# Hardverski_dizajn_ver2.net
KiCad netlist of a schematic drawn in EasyEDA
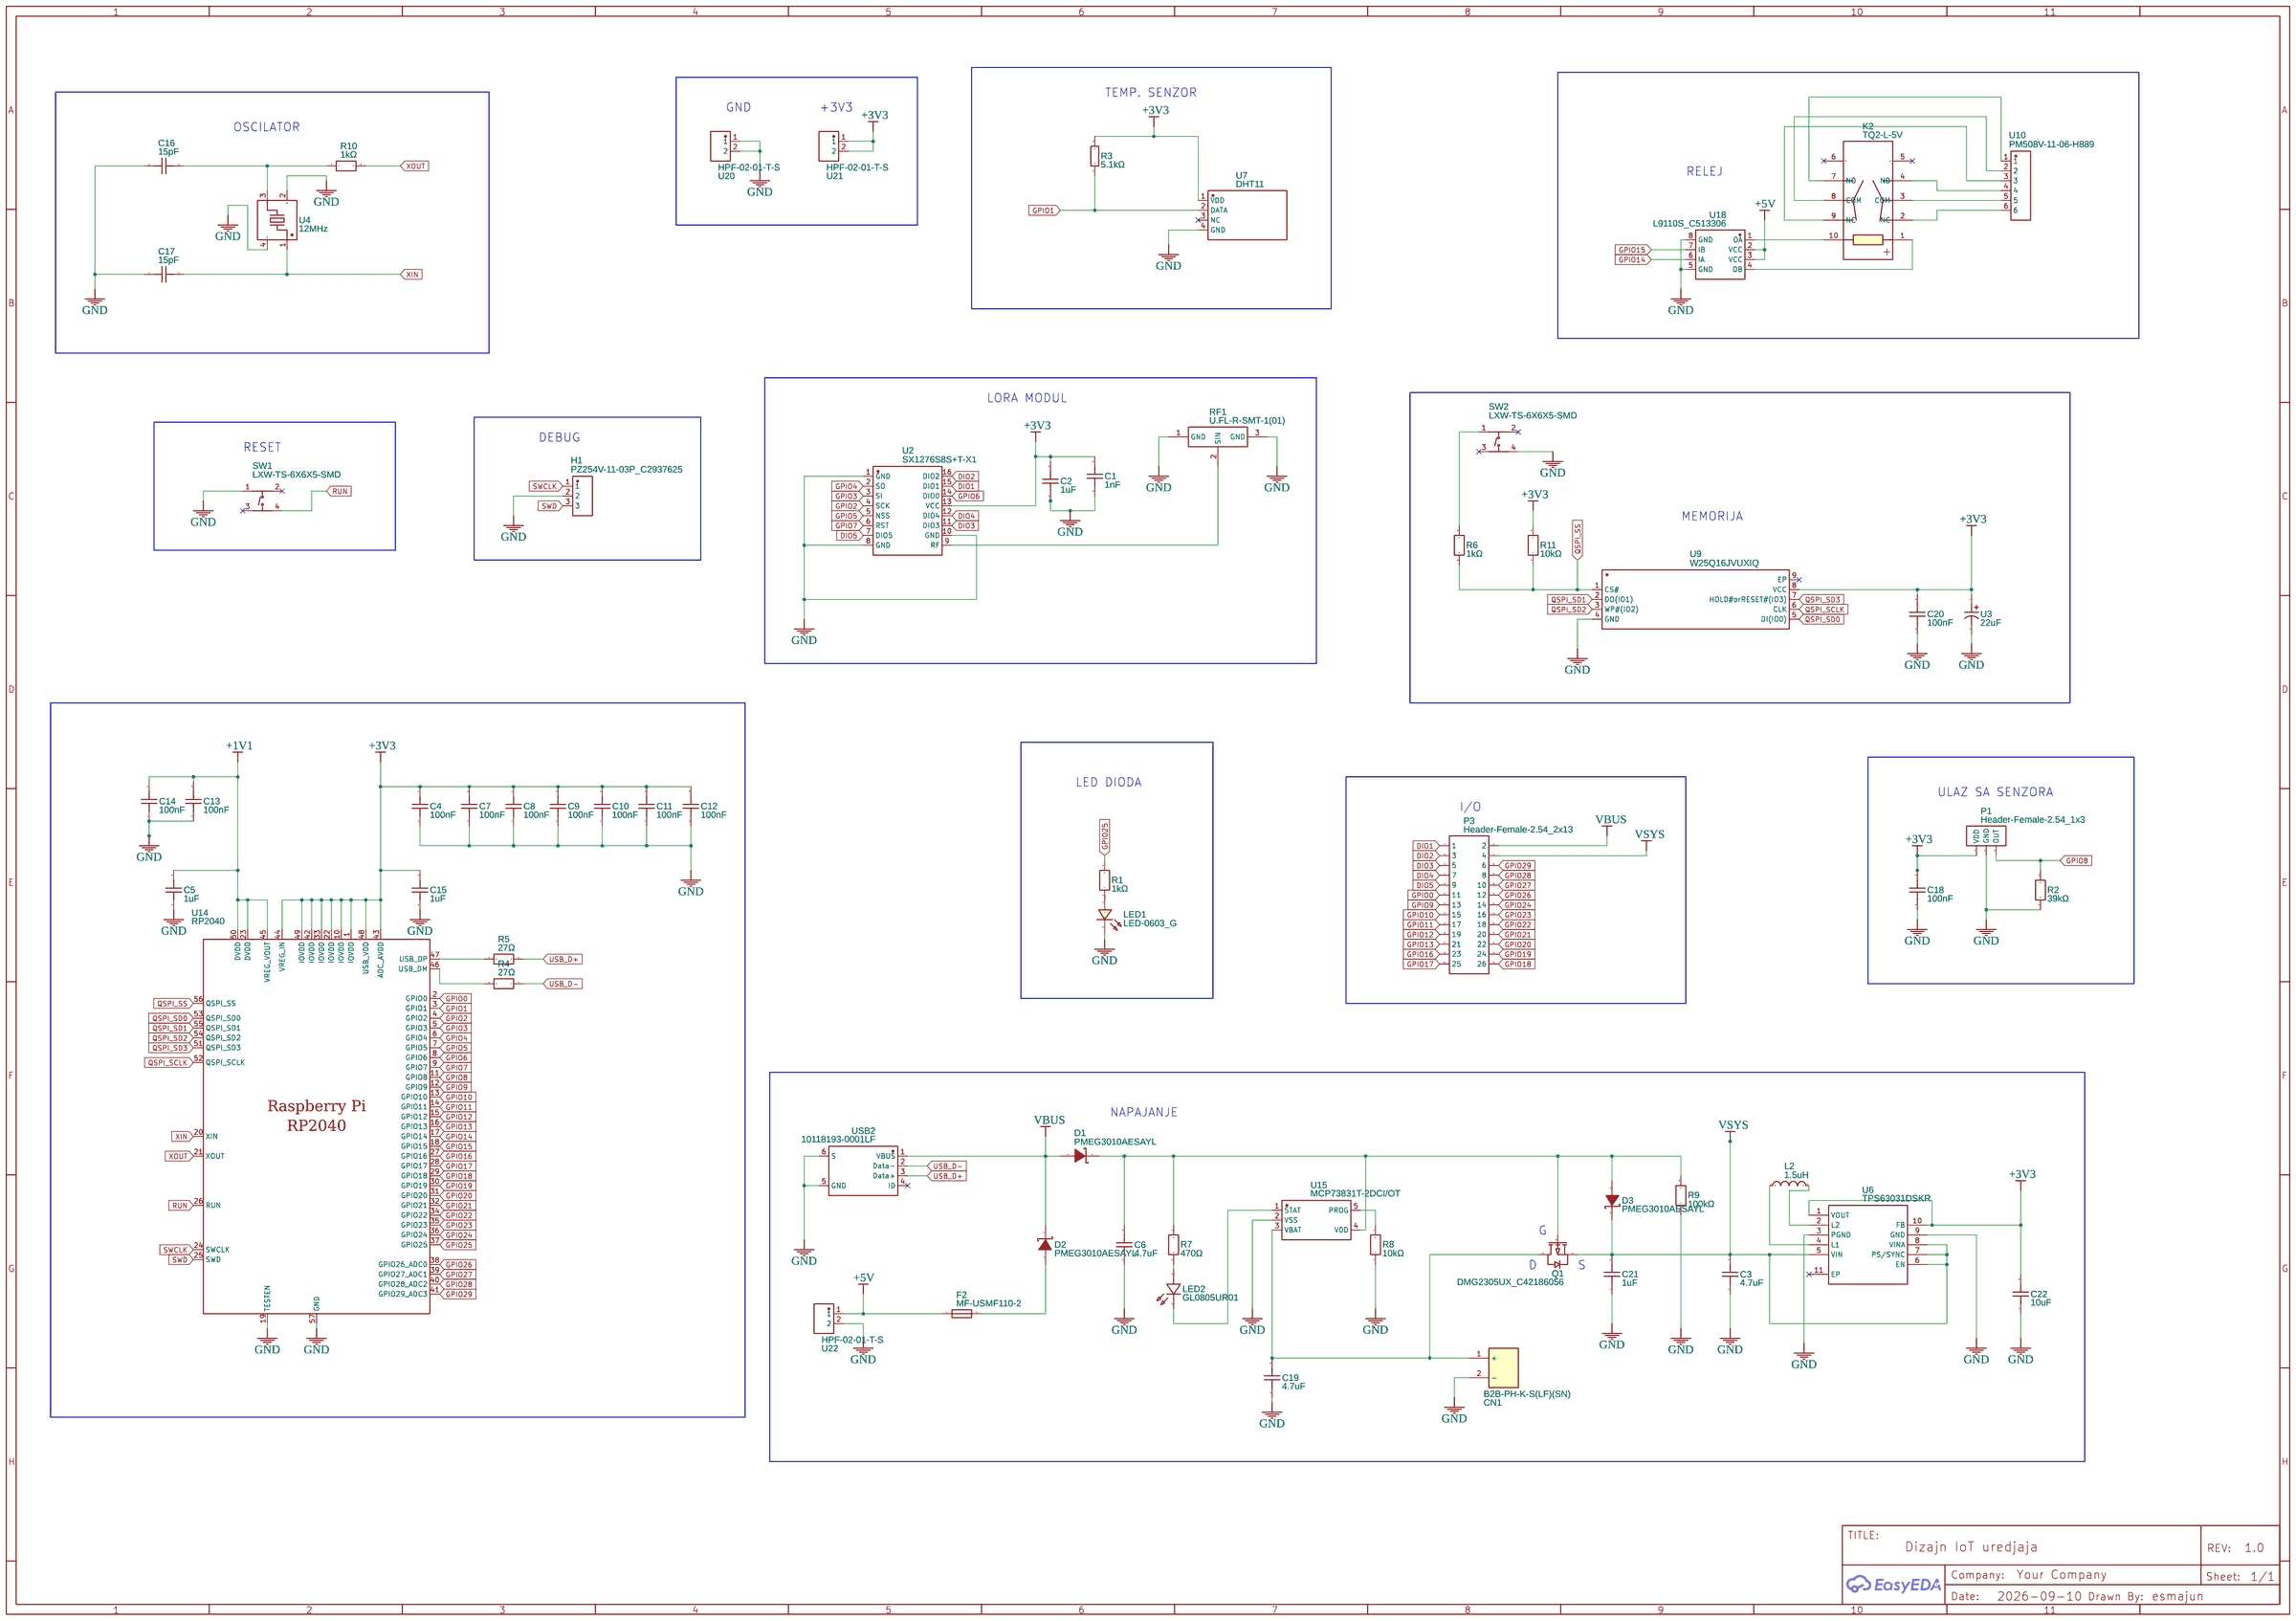
[diagram p0: schematic sheet]

(export (version "E")
  (design (tool "Eeschema 10.0.6"))
  (components
    (comp (ref "C1") (value "1nF") (libsource (lib "") (part "C_0805_US_1")))
    (comp (ref "C2") (value "1uF") (libsource (lib "") (part "C_0805_US_1")))
    (comp (ref "C3") (value "4.7uF") (libsource (lib "") (part "C_0805_US_1")))
    (comp (ref "C4") (value "100nF") (libsource (lib "") (part "C_0805_US_1")))
    (comp (ref "C5") (value "1uF") (libsource (lib "") (part "C_0805_US_1")))
    (comp (ref "C6") (value "4.7uF") (libsource (lib "") (part "C_0805_US_1")))
    (comp (ref "C7") (value "100nF") (libsource (lib "") (part "C_0805_US_1")))
    (comp (ref "C8") (value "100nF") (libsource (lib "") (part "C_0805_US_1")))
    (comp (ref "C9") (value "100nF") (libsource (lib "") (part "C_0805_US_1")))
    (comp (ref "C10") (value "100nF") (libsource (lib "") (part "C_0805_US_1")))
    (comp (ref "C11") (value "100nF") (libsource (lib "") (part "C_0805_US_1")))
    (comp (ref "C12") (value "100nF") (libsource (lib "") (part "C_0805_US_1")))
    (comp (ref "C13") (value "100nF") (libsource (lib "") (part "C_0805_US_1")))
    (comp (ref "C14") (value "100nF") (libsource (lib "") (part "C_0805_US_1")))
    (comp (ref "C15") (value "1uF") (libsource (lib "") (part "C_0805_US_1")))
    (comp (ref "C16") (value "15pF") (libsource (lib "") (part "C_0805_US")))
    (comp (ref "C17") (value "15pF") (libsource (lib "") (part "C_0805_US")))
    (comp (ref "C18") (value "100nF") (libsource (lib "") (part "C_0805_US_1")))
    (comp (ref "C19") (value "4.7uF") (libsource (lib "") (part "C_0805_US_1")))
    (comp (ref "C20") (value "100nF") (libsource (lib "") (part "C_0805_US_1")))
    (comp (ref "C21") (value "1uF") (libsource (lib "") (part "C_0805_US_1")))
    (comp (ref "C22") (value "10uF") (libsource (lib "") (part "C_0805_US_1")))
    (comp (ref "CN1")
      (value "B2B-PH-K-S(LF)(SN)")
      (fields (field (name "Manufacturer") "JST"))
      (libsource (lib "") (part "B2B-PH-K-S(LF)(SN)"))
    )
    (comp (ref "D1")
      (value "PMEG3010AESAYL")
      (fields (field (name "Manufacturer") "Nexperia(安世)"))
      (libsource (lib "") (part "PMEG3010AESAYL"))
    )
    (comp (ref "D2")
      (value "PMEG3010AESAYL")
      (fields (field (name "Manufacturer") "Nexperia(安世)"))
      (libsource (lib "") (part "PMEG3010AESAYL_2"))
    )
    (comp (ref "D3")
      (value "PMEG3010AESAYL")
      (fields (field (name "Manufacturer") "Nexperia(安世)"))
      (libsource (lib "") (part "PMEG3010AESAYL_1"))
    )
    (comp (ref "F2")
      (value "MF-USMF110-2")
      (fields (field (name "Manufacturer") "BOURNS"))
      (libsource (lib "") (part "MF-USMF110-2"))
    )
    (comp (ref "H1")
      (value "PZ254V-11-03P_C2937625")
      (fields (field (name "Manufacturer Part") "PZ254V-11-03P") (field (name "Manufacturer") "XFCN(兴飞)"))
      (libsource (lib "") (part "PZ254V-11-03P_C2937625"))
    )
    (comp (ref "K2")
      (value "TQ2-L-5V")
      (fields (field (name "Manufacturer") "PANASONIC(松下)"))
      (libsource (lib "") (part "TQ2-L-5V"))
    )
    (comp (ref "L2")
      (value "1.5uH")
      (fields
        (field (name "Manufacturer Part") "SLW201610P1R5MST")
        (field (name "Manufacturer") "Sunltech(顺磁)")
      )
      (libsource (lib "") (part "SLW201610P1R5MST"))
    )
    (comp (ref "LED1")
      (value "LED-0603_G")
      (fields
        (field (name "Manufacturer Part") "19-217/GHC-YR1S2/3T")
        (field (name "Manufacturer") "EVERLIGHT(台湾亿光)")
      )
      (libsource (lib "") (part "LED-0603_G"))
    )
    (comp (ref "LED2")
      (value "GL0805UR01")
      (fields (field (name "Manufacturer") "Guiguang light(桂光光电)"))
      (libsource (lib "") (part "GL0805UR01"))
    )
    (comp (ref "P1")
      (value "Header-Female-2.54_1x3")
      (fields (field (name "Manufacturer Part") "2.54-1*3P母") (field (name "Manufacturer") "BOOMELE(博穆精密)"))
      (libsource (lib "") (part "Header-Female-2.54_1x3"))
    )
    (comp (ref "P3")
      (value "Header-Female-2.54_2x13")
      (fields (field (name "Manufacturer Part") "2.54-2*13P母") (field (name "Manufacturer") "BOOMELE(博穆精密)"))
      (libsource (lib "") (part "Header-Female-2.54_2x13"))
    )
    (comp (ref "Q1")
      (value "DMG2305UX_C42186056")
      (fields (field (name "Manufacturer Part") "DMG2305UX") (field (name "Manufacturer") "GOODWORK(固得沃克)"))
      (libsource (lib "") (part "DMG2305UX_C42186056"))
    )
    (comp (ref "R1") (value "1kΩ") (libsource (lib "") (part "R_0805_EU")))
    (comp (ref "R2") (value "39kΩ") (libsource (lib "") (part "R_0805_EU")))
    (comp (ref "R3")
      (value "5.1kΩ")
      (fields (field (name "Manufacturer Part") "RMC08055.1K5%N") (field (name "Manufacturer") "Tyohm(幸亚电阻)"))
      (libsource (lib "") (part "RMC08055.1K5%N"))
    )
    (comp (ref "R4") (value "27Ω") (libsource (lib "") (part "R_0805_EU_1")))
    (comp (ref "R5") (value "27Ω") (libsource (lib "") (part "R_0805_EU_1")))
    (comp (ref "R6") (value "1kΩ") (libsource (lib "") (part "R_0805_EU")))
    (comp (ref "R7") (value "470Ω") (libsource (lib "") (part "R_0805_EU")))
    (comp (ref "R8") (value "10kΩ") (libsource (lib "") (part "R_0805_EU")))
    (comp (ref "R9") (value "100kΩ") (libsource (lib "") (part "R_0805_EU")))
    (comp (ref "R10") (value "1kΩ") (libsource (lib "") (part "R_0805_EU_2")))
    (comp (ref "R11") (value "10kΩ") (libsource (lib "") (part "R_0805_EU")))
    (comp (ref "RF1")
      (value "U.FL-R-SMT-1(01)")
      (fields (field (name "Manufacturer") "HRS(广濑)"))
      (libsource (lib "") (part "U.FL-R-SMT-1(01)"))
    )
    (comp (ref "SW1")
      (value "LXW-TS-6X6X5-SMD")
      (fields (field (name "Manufacturer") "LXWCONN(连兴旺电子)"))
      (libsource (lib "") (part "LXW-TS-6X6X5-SMD"))
    )
    (comp (ref "SW2")
      (value "LXW-TS-6X6X5-SMD")
      (fields (field (name "Manufacturer") "LXWCONN(连兴旺电子)"))
      (libsource (lib "") (part "LXW-TS-6X6X5-SMD"))
    )
    (comp (ref "U2")
      (value "SX1276S8S+T-X1")
      (fields (field (name "Manufacturer") "Vollgo(沃进)"))
      (libsource (lib "") (part "SX1276S8S+T-X1"))
    )
    (comp (ref "U3")
      (value "22uF")
      (fields (field (name "Manufacturer Part") "189RV0020") (field (name "Manufacturer") "KNSCHA(科尼盛)"))
      (libsource (lib "") (part "189RV0020"))
    )
    (comp (ref "U4")
      (value "12MHz")
      (fields (field (name "Manufacturer Part") "ABM8-272-T3") (field (name "Manufacturer") "ABRACON"))
      (libsource (lib "") (part "ABM8-272-T3_C20625731"))
    )
    (comp (ref "U6")
      (value "TPS63031DSKR")
      (fields (field (name "Manufacturer") "TI(德州仪器)"))
      (libsource (lib "") (part "TPS63031DSKR"))
    )
    (comp (ref "U7")
      (value "DHT11")
      (fields (field (name "Manufacturer") "广州奥松"))
      (libsource (lib "") (part "DHT11"))
    )
    (comp (ref "U9")
      (value "W25Q16JVUXIQ")
      (fields (field (name "Manufacturer") "Winbond(华邦)"))
      (libsource (lib "") (part "W25Q16JVUXIQ"))
    )
    (comp (ref "U10")
      (value "PM508V-11-06-H889")
      (fields (field (name "Manufacturer") "XFCN(兴飞)"))
      (libsource (lib "") (part "PM508V-11-06-H889"))
    )
    (comp (ref "U14")
      (value "RP2040")
      (fields (field (name "Manufacturer") "Raspberry Pi(树莓派)"))
      (libsource (lib "") (part "RP2040"))
    )
    (comp (ref "U15")
      (value "MCP73831T-2DCI/OT")
      (fields (field (name "Manufacturer") "MICROCHIP(美国微芯)"))
      (libsource (lib "") (part "MCP73831T-2DCI/OT"))
    )
    (comp (ref "U18")
      (value "L9110S_C513306")
      (fields (field (name "Manufacturer Part") "L9110S") (field (name "Manufacturer") "Mixic(中科芯亿达)"))
      (libsource (lib "") (part "L9110S_C513306"))
    )
    (comp (ref "U20")
      (value "HPF-02-01-T-S")
      (fields (field (name "Manufacturer") "SAMTEC"))
      (libsource (lib "") (part "HPF-02-01-T-S"))
    )
    (comp (ref "U21")
      (value "HPF-02-01-T-S")
      (fields (field (name "Manufacturer") "SAMTEC"))
      (libsource (lib "") (part "HPF-02-01-T-S"))
    )
    (comp (ref "U22")
      (value "HPF-02-01-T-S")
      (fields (field (name "Manufacturer") "SAMTEC"))
      (libsource (lib "") (part "HPF-02-01-T-S"))
    )
    (comp (ref "USB2")
      (value "10118193-0001LF")
      (fields (field (name "Manufacturer") "Amphenol"))
      (libsource (lib "") (part "10118193-0001LF"))
    )
  )
  (nets
    (net (code "1") (name "+1V1") (class "Default")
      (node (ref "C13") (pin "2") (pinfunction "2_2") (pintype "unspecified"))
      (node (ref "C14") (pin "2") (pinfunction "2_2") (pintype "unspecified"))
      (node (ref "C5") (pin "2") (pinfunction "2_2") (pintype "unspecified"))
      (node (ref "U14") (pin "23") (pinfunction "DVDD_23") (pintype "bidirectional"))
      (node (ref "U14") (pin "45") (pinfunction "VREG_VOUT_45") (pintype "bidirectional"))
      (node (ref "U14") (pin "50") (pinfunction "DVDD_50") (pintype "bidirectional"))
    )
    (net (code "2") (name "+3V3") (class "Default")
      (node (ref "C1") (pin "2") (pinfunction "2_2") (pintype "unspecified"))
      (node (ref "C10") (pin "2") (pinfunction "2_2") (pintype "unspecified"))
      (node (ref "C11") (pin "2") (pinfunction "2_2") (pintype "unspecified"))
      (node (ref "C12") (pin "2") (pinfunction "2_2") (pintype "unspecified"))
      (node (ref "C15") (pin "2") (pinfunction "2_2") (pintype "unspecified"))
      (node (ref "C18") (pin "2") (pinfunction "2_2") (pintype "unspecified"))
      (node (ref "C2") (pin "2") (pinfunction "2_2") (pintype "unspecified"))
      (node (ref "C20") (pin "2") (pinfunction "2_2") (pintype "unspecified"))
      (node (ref "C22") (pin "2") (pinfunction "2_2") (pintype "unspecified"))
      (node (ref "C4") (pin "2") (pinfunction "2_2") (pintype "unspecified"))
      (node (ref "C7") (pin "2") (pinfunction "2_2") (pintype "unspecified"))
      (node (ref "C8") (pin "2") (pinfunction "2_2") (pintype "unspecified"))
      (node (ref "C9") (pin "2") (pinfunction "2_2") (pintype "unspecified"))
      (node (ref "P1") (pin "1") (pinfunction "VDD_1") (pintype "input"))
      (node (ref "R11") (pin "2") (pinfunction "2_2") (pintype "unspecified"))
      (node (ref "R3") (pin "2") (pinfunction "2_2") (pintype "unspecified"))
      (node (ref "U14") (pin "1") (pinfunction "IOVDD_1") (pintype "bidirectional"))
      (node (ref "U14") (pin "10") (pinfunction "IOVDD_10") (pintype "bidirectional"))
      (node (ref "U14") (pin "22") (pinfunction "IOVDD_22") (pintype "bidirectional"))
      (node (ref "U14") (pin "33") (pinfunction "IOVDD_33") (pintype "bidirectional"))
      (node (ref "U14") (pin "42") (pinfunction "IOVDD_42") (pintype "bidirectional"))
      (node (ref "U14") (pin "43") (pinfunction "ADC_AVDD_43") (pintype "bidirectional"))
      (node (ref "U14") (pin "44") (pinfunction "VREG_IN_44") (pintype "bidirectional"))
      (node (ref "U14") (pin "48") (pinfunction "USB_VDD_48") (pintype "bidirectional"))
      (node (ref "U14") (pin "49") (pinfunction "IOVDD_49") (pintype "bidirectional"))
      (node (ref "U2") (pin "13") (pinfunction "VCC_13") (pintype "unspecified"))
      (node (ref "U21") (pin "1") (pinfunction "1_1") (pintype "unspecified"))
      (node (ref "U21") (pin "2") (pinfunction "2_2") (pintype "unspecified"))
      (node (ref "U3") (pin "1") (pinfunction "1_1") (pintype "input"))
      (node (ref "U6") (pin "1") (pinfunction "VOUT_1") (pintype "unspecified"))
      (node (ref "U6") (pin "10") (pinfunction "FB_10") (pintype "unspecified"))
      (node (ref "U7") (pin "1") (pinfunction "VDD_1") (pintype "unspecified"))
      (node (ref "U9") (pin "8") (pinfunction "VCC_8") (pintype "unspecified"))
    )
    (net (code "3") (name "+5V") (class "Default")
      (node (ref "F2") (pin "1") (pinfunction "1_1") (pintype "unspecified"))
      (node (ref "U18") (pin "2") (pinfunction "VCC_2") (pintype "unspecified"))
      (node (ref "U18") (pin "3") (pinfunction "VCC_3") (pintype "unspecified"))
      (node (ref "U22") (pin "1") (pinfunction "1_1") (pintype "unspecified"))
    )
    (net (code "4") (name "DIO1") (class "Default")
      (node (ref "P3") (pin "1") (pinfunction "1_1") (pintype "input"))
      (node (ref "U2") (pin "15") (pinfunction "DIO1_15") (pintype "unspecified"))
    )
    (net (code "5") (name "DIO2") (class "Default")
      (node (ref "P3") (pin "3") (pinfunction "3_3") (pintype "input"))
      (node (ref "U2") (pin "16") (pinfunction "DIO2_16") (pintype "unspecified"))
    )
    (net (code "6") (name "DIO3") (class "Default")
      (node (ref "P3") (pin "5") (pinfunction "5_5") (pintype "input"))
      (node (ref "U2") (pin "11") (pinfunction "DIO3_11") (pintype "unspecified"))
    )
    (net (code "7") (name "DIO4") (class "Default")
      (node (ref "P3") (pin "7") (pinfunction "7_7") (pintype "input"))
      (node (ref "U2") (pin "12") (pinfunction "DIO4_12") (pintype "unspecified"))
    )
    (net (code "8") (name "DIO5") (class "Default")
      (node (ref "P3") (pin "9") (pinfunction "9_9") (pintype "input"))
      (node (ref "U2") (pin "7") (pinfunction "DIO5_7") (pintype "unspecified"))
    )
    (net (code "9") (name "GND") (class "Default")
      (node (ref "C1") (pin "1") (pinfunction "1_1") (pintype "unspecified"))
      (node (ref "C10") (pin "1") (pinfunction "1_1") (pintype "unspecified"))
      (node (ref "C11") (pin "1") (pinfunction "1_1") (pintype "unspecified"))
      (node (ref "C12") (pin "1") (pinfunction "1_1") (pintype "unspecified"))
      (node (ref "C13") (pin "1") (pinfunction "1_1") (pintype "unspecified"))
      (node (ref "C14") (pin "1") (pinfunction "1_1") (pintype "unspecified"))
      (node (ref "C15") (pin "1") (pinfunction "1_1") (pintype "unspecified"))
      (node (ref "C16") (pin "1") (pinfunction "1_1") (pintype "unspecified"))
      (node (ref "C17") (pin "1") (pinfunction "1_1") (pintype "unspecified"))
      (node (ref "C18") (pin "1") (pinfunction "1_1") (pintype "unspecified"))
      (node (ref "C19") (pin "1") (pinfunction "1_1") (pintype "unspecified"))
      (node (ref "C2") (pin "1") (pinfunction "1_1") (pintype "unspecified"))
      (node (ref "C20") (pin "1") (pinfunction "1_1") (pintype "unspecified"))
      (node (ref "C21") (pin "1") (pinfunction "1_1") (pintype "unspecified"))
      (node (ref "C22") (pin "1") (pinfunction "1_1") (pintype "unspecified"))
      (node (ref "C3") (pin "1") (pinfunction "1_1") (pintype "unspecified"))
      (node (ref "C4") (pin "1") (pinfunction "1_1") (pintype "unspecified"))
      (node (ref "C5") (pin "1") (pinfunction "1_1") (pintype "unspecified"))
      (node (ref "C6") (pin "1") (pinfunction "1_1") (pintype "unspecified"))
      (node (ref "C7") (pin "1") (pinfunction "1_1") (pintype "unspecified"))
      (node (ref "C8") (pin "1") (pinfunction "1_1") (pintype "unspecified"))
      (node (ref "C9") (pin "1") (pinfunction "1_1") (pintype "unspecified"))
      (node (ref "CN1") (pin "2") (pinfunction "-_2") (pintype "input"))
      (node (ref "H1") (pin "2") (pinfunction "2_2") (pintype "unspecified"))
      (node (ref "LED1") (pin "2") (pinfunction "2_2") (pintype "unspecified"))
      (node (ref "P1") (pin "2") (pinfunction "GND_2") (pintype "input"))
      (node (ref "R2") (pin "1") (pinfunction "1_1") (pintype "unspecified"))
      (node (ref "R8") (pin "1") (pinfunction "1_1") (pintype "unspecified"))
      (node (ref "R9") (pin "1") (pinfunction "1_1") (pintype "unspecified"))
      (node (ref "RF1") (pin "1") (pinfunction "GND_1") (pintype "unspecified"))
      (node (ref "RF1") (pin "3") (pinfunction "GND_3") (pintype "unspecified"))
      (node (ref "SW1") (pin "1") (pinfunction "1_1") (pintype "unspecified"))
      (node (ref "SW2") (pin "4") (pinfunction "4_4") (pintype "unspecified"))
      (node (ref "U14") (pin "19") (pinfunction "TESTEN_19") (pintype "unspecified"))
      (node (ref "U14") (pin "57") (pinfunction "GND_57") (pintype "bidirectional"))
      (node (ref "U15") (pin "2") (pinfunction "VSS_2") (pintype "unspecified"))
      (node (ref "U18") (pin "5") (pinfunction "GND_5") (pintype "unspecified"))
      (node (ref "U18") (pin "8") (pinfunction "GND_8") (pintype "unspecified"))
      (node (ref "U2") (pin "1") (pinfunction "GND_1") (pintype "unspecified"))
      (node (ref "U2") (pin "10") (pinfunction "GND_10") (pintype "unspecified"))
      (node (ref "U2") (pin "8") (pinfunction "GND_8") (pintype "unspecified"))
      (node (ref "U20") (pin "1") (pinfunction "1_1") (pintype "unspecified"))
      (node (ref "U20") (pin "2") (pinfunction "2_2") (pintype "unspecified"))
      (node (ref "U22") (pin "2") (pinfunction "2_2") (pintype "unspecified"))
      (node (ref "U3") (pin "2") (pinfunction "2_2") (pintype "input"))
      (node (ref "U4") (pin "2") (pinfunction "GND_2") (pintype "input"))
      (node (ref "U4") (pin "4") (pinfunction "GND_4") (pintype "input"))
      (node (ref "U6") (pin "3") (pinfunction "PGND_3") (pintype "unspecified"))
      (node (ref "U6") (pin "9") (pinfunction "GND_9") (pintype "unspecified"))
      (node (ref "U7") (pin "4") (pinfunction "GND_4") (pintype "unspecified"))
      (node (ref "U9") (pin "4") (pinfunction "GND_4") (pintype "unspecified"))
      (node (ref "USB2") (pin "5") (pinfunction "GND_5") (pintype "unspecified"))
      (node (ref "USB2") (pin "6") (pinfunction "S_6") (pintype "unspecified"))
    )
    (net (code "10") (name "GPIO0") (class "Default")
      (node (ref "P3") (pin "11") (pinfunction "11_11") (pintype "input"))
      (node (ref "U14") (pin "2") (pinfunction "GPIO0_2") (pintype "bidirectional"))
    )
    (net (code "11") (name "GPIO1") (class "Default")
      (node (ref "R3") (pin "1") (pinfunction "1_1") (pintype "unspecified"))
      (node (ref "U14") (pin "3") (pinfunction "GPIO1_3") (pintype "bidirectional"))
      (node (ref "U7") (pin "2") (pinfunction "DATA_2") (pintype "unspecified"))
    )
    (net (code "12") (name "GPIO2") (class "Default")
      (node (ref "U14") (pin "4") (pinfunction "GPIO2_4") (pintype "bidirectional"))
      (node (ref "U2") (pin "4") (pinfunction "SCK_4") (pintype "unspecified"))
    )
    (net (code "13") (name "GPIO3") (class "Default")
      (node (ref "U14") (pin "5") (pinfunction "GPIO3_5") (pintype "bidirectional"))
      (node (ref "U2") (pin "3") (pinfunction "SI_3") (pintype "unspecified"))
    )
    (net (code "14") (name "GPIO4") (class "Default")
      (node (ref "U14") (pin "6") (pinfunction "GPIO4_6") (pintype "bidirectional"))
      (node (ref "U2") (pin "2") (pinfunction "SO_2") (pintype "unspecified"))
    )
    (net (code "15") (name "GPIO5") (class "Default")
      (node (ref "U14") (pin "7") (pinfunction "GPIO5_7") (pintype "bidirectional"))
      (node (ref "U2") (pin "5") (pinfunction "NSS_5") (pintype "unspecified"))
    )
    (net (code "16") (name "GPIO6") (class "Default")
      (node (ref "U14") (pin "8") (pinfunction "GPIO6_8") (pintype "bidirectional"))
      (node (ref "U2") (pin "14") (pinfunction "DIO0_14") (pintype "unspecified"))
    )
    (net (code "17") (name "GPIO7") (class "Default")
      (node (ref "U14") (pin "9") (pinfunction "GPIO7_9") (pintype "bidirectional"))
      (node (ref "U2") (pin "6") (pinfunction "RST_6") (pintype "unspecified"))
    )
    (net (code "18") (name "GPIO8") (class "Default")
      (node (ref "P1") (pin "3") (pinfunction "OUT_3") (pintype "input"))
      (node (ref "R2") (pin "2") (pinfunction "2_2") (pintype "unspecified"))
      (node (ref "U14") (pin "11") (pinfunction "GPIO8_11") (pintype "bidirectional"))
    )
    (net (code "19") (name "GPIO9") (class "Default")
      (node (ref "P3") (pin "13") (pinfunction "13_13") (pintype "input"))
      (node (ref "U14") (pin "12") (pinfunction "GPIO9_12") (pintype "bidirectional"))
    )
    (net (code "20") (name "GPIO10") (class "Default")
      (node (ref "P3") (pin "15") (pinfunction "15_15") (pintype "input"))
      (node (ref "U14") (pin "13") (pinfunction "GPIO10_13") (pintype "bidirectional"))
    )
    (net (code "21") (name "GPIO11") (class "Default")
      (node (ref "P3") (pin "17") (pinfunction "17_17") (pintype "input"))
      (node (ref "U14") (pin "14") (pinfunction "GPIO11_14") (pintype "bidirectional"))
    )
    (net (code "22") (name "GPIO12") (class "Default")
      (node (ref "P3") (pin "19") (pinfunction "19_19") (pintype "input"))
      (node (ref "U14") (pin "15") (pinfunction "GPIO12_15") (pintype "bidirectional"))
    )
    (net (code "23") (name "GPIO13") (class "Default")
      (node (ref "P3") (pin "21") (pinfunction "21_21") (pintype "input"))
      (node (ref "U14") (pin "16") (pinfunction "GPIO13_16") (pintype "bidirectional"))
    )
    (net (code "24") (name "GPIO14") (class "Default")
      (node (ref "U14") (pin "17") (pinfunction "GPIO14_17") (pintype "bidirectional"))
      (node (ref "U18") (pin "6") (pinfunction "IA_6") (pintype "unspecified"))
    )
    (net (code "25") (name "GPIO15") (class "Default")
      (node (ref "U14") (pin "18") (pinfunction "GPIO15_18") (pintype "bidirectional"))
      (node (ref "U18") (pin "7") (pinfunction "IB_7") (pintype "unspecified"))
    )
    (net (code "26") (name "GPIO16") (class "Default")
      (node (ref "P3") (pin "23") (pinfunction "23_23") (pintype "input"))
      (node (ref "U14") (pin "27") (pinfunction "GPIO16_27") (pintype "bidirectional"))
    )
    (net (code "27") (name "GPIO17") (class "Default")
      (node (ref "P3") (pin "25") (pinfunction "25_25") (pintype "input"))
      (node (ref "U14") (pin "28") (pinfunction "GPIO17_28") (pintype "bidirectional"))
    )
    (net (code "28") (name "GPIO18") (class "Default")
      (node (ref "P3") (pin "26") (pinfunction "26_26") (pintype "input"))
      (node (ref "U14") (pin "29") (pinfunction "GPIO18_29") (pintype "bidirectional"))
    )
    (net (code "29") (name "GPIO19") (class "Default")
      (node (ref "P3") (pin "24") (pinfunction "24_24") (pintype "input"))
      (node (ref "U14") (pin "30") (pinfunction "GPIO19_30") (pintype "bidirectional"))
    )
    (net (code "30") (name "GPIO20") (class "Default")
      (node (ref "P3") (pin "22") (pinfunction "22_22") (pintype "input"))
      (node (ref "U14") (pin "31") (pinfunction "GPIO20_31") (pintype "bidirectional"))
    )
    (net (code "31") (name "GPIO21") (class "Default")
      (node (ref "P3") (pin "20") (pinfunction "20_20") (pintype "input"))
      (node (ref "U14") (pin "32") (pinfunction "GPIO21_32") (pintype "bidirectional"))
    )
    (net (code "32") (name "GPIO22") (class "Default")
      (node (ref "P3") (pin "18") (pinfunction "18_18") (pintype "input"))
      (node (ref "U14") (pin "34") (pinfunction "GPIO22_34") (pintype "bidirectional"))
    )
    (net (code "33") (name "GPIO23") (class "Default")
      (node (ref "P3") (pin "16") (pinfunction "16_16") (pintype "input"))
      (node (ref "U14") (pin "35") (pinfunction "GPIO23_35") (pintype "bidirectional"))
    )
    (net (code "34") (name "GPIO24") (class "Default")
      (node (ref "P3") (pin "14") (pinfunction "14_14") (pintype "input"))
      (node (ref "U14") (pin "36") (pinfunction "GPIO24_36") (pintype "bidirectional"))
    )
    (net (code "35") (name "GPIO25") (class "Default")
      (node (ref "R1") (pin "2") (pinfunction "2_2") (pintype "unspecified"))
      (node (ref "U14") (pin "37") (pinfunction "GPIO25_37") (pintype "bidirectional"))
    )
    (net (code "36") (name "GPIO26") (class "Default")
      (node (ref "P3") (pin "12") (pinfunction "12_12") (pintype "input"))
      (node (ref "U14") (pin "38") (pinfunction "GPIO26_ADC0_38") (pintype "bidirectional"))
    )
    (net (code "37") (name "GPIO27") (class "Default")
      (node (ref "P3") (pin "10") (pinfunction "10_10") (pintype "input"))
      (node (ref "U14") (pin "39") (pinfunction "GPIO27_ADC1_39") (pintype "bidirectional"))
    )
    (net (code "38") (name "GPIO28") (class "Default")
      (node (ref "P3") (pin "8") (pinfunction "8_8") (pintype "input"))
      (node (ref "U14") (pin "40") (pinfunction "GPIO28_ADC2_40") (pintype "bidirectional"))
    )
    (net (code "39") (name "GPIO29") (class "Default")
      (node (ref "P3") (pin "6") (pinfunction "6_6") (pintype "input"))
      (node (ref "U14") (pin "41") (pinfunction "GPIO29_ADC3_41") (pintype "bidirectional"))
    )
    (net (code "40") (name "Net-(C16-Pad2)") (class "Default")
      (node (ref "C16") (pin "2") (pinfunction "2_2") (pintype "unspecified"))
      (node (ref "R10") (pin "1") (pinfunction "1_1") (pintype "unspecified"))
      (node (ref "U4") (pin "3") (pinfunction "3_3") (pintype "input"))
    )
    (net (code "41") (name "Net-(CN1-+)") (class "Default")
      (node (ref "C19") (pin "2") (pinfunction "2_2") (pintype "unspecified"))
      (node (ref "CN1") (pin "1") (pinfunction "+_1") (pintype "input"))
      (node (ref "Q1") (pin "3") (pinfunction "D_3") (pintype "unspecified"))
      (node (ref "U15") (pin "3") (pinfunction "VBAT_3") (pintype "unspecified"))
    )
    (net (code "42") (name "Net-(D1-K)") (class "Default")
      (node (ref "C6") (pin "2") (pinfunction "2_2") (pintype "unspecified"))
      (node (ref "D1") (pin "1") (pinfunction "K_1") (pintype "unspecified"))
      (node (ref "D3") (pin "2") (pinfunction "A_2") (pintype "unspecified"))
      (node (ref "Q1") (pin "1") (pinfunction "G_1") (pintype "unspecified"))
      (node (ref "R7") (pin "2") (pinfunction "2_2") (pintype "unspecified"))
      (node (ref "R9") (pin "2") (pinfunction "2_2") (pintype "unspecified"))
      (node (ref "U15") (pin "4") (pinfunction "VDD_4") (pintype "unspecified"))
    )
    (net (code "43") (name "Net-(D2-A)") (class "Default")
      (node (ref "D2") (pin "2") (pinfunction "A_2") (pintype "unspecified"))
      (node (ref "F2") (pin "2") (pinfunction "2_2") (pintype "unspecified"))
    )
    (net (code "44") (name "Net-(K2-COM-Pad3)") (class "Default")
      (node (ref "K2") (pin "3") (pinfunction "COM_3") (pintype "unspecified"))
      (node (ref "U10") (pin "5") (pinfunction "5_5") (pintype "unspecified"))
    )
    (net (code "45") (name "Net-(K2-COM-Pad8)") (class "Default")
      (node (ref "K2") (pin "8") (pinfunction "COM_8") (pintype "unspecified"))
      (node (ref "U10") (pin "2") (pinfunction "2_2") (pintype "unspecified"))
    )
    (net (code "46") (name "Net-(K2-NC-Pad2)") (class "Default")
      (node (ref "K2") (pin "2") (pinfunction "NC_2") (pintype "unspecified"))
      (node (ref "U10") (pin "6") (pinfunction "6_6") (pintype "unspecified"))
    )
    (net (code "47") (name "Net-(K2-NC-Pad9)") (class "Default")
      (node (ref "K2") (pin "9") (pinfunction "NC_9") (pintype "unspecified"))
      (node (ref "U10") (pin "3") (pinfunction "3_3") (pintype "unspecified"))
    )
    (net (code "48") (name "Net-(K2-NO-Pad4)") (class "Default")
      (node (ref "K2") (pin "4") (pinfunction "NO_4") (pintype "unspecified"))
      (node (ref "U10") (pin "4") (pinfunction "4_4") (pintype "unspecified"))
    )
    (net (code "49") (name "Net-(K2-NO-Pad7)") (class "Default")
      (node (ref "K2") (pin "7") (pinfunction "NO_7") (pintype "unspecified"))
      (node (ref "U10") (pin "1") (pinfunction "1_1") (pintype "unspecified"))
    )
    (net (code "50") (name "Net-(LED1-Pad1)") (class "Default")
      (node (ref "LED1") (pin "1") (pinfunction "1_1") (pintype "unspecified"))
      (node (ref "R1") (pin "1") (pinfunction "1_1") (pintype "unspecified"))
    )
    (net (code "51") (name "Net-(LED2-A)") (class "Default")
      (node (ref "LED2") (pin "1") (pinfunction "A_1") (pintype "unspecified"))
      (node (ref "R7") (pin "1") (pinfunction "1_1") (pintype "unspecified"))
    )
    (net (code "52") (name "Net-(LED2-C)") (class "Default")
      (node (ref "LED2") (pin "2") (pinfunction "C_2") (pintype "unspecified"))
      (node (ref "U15") (pin "1") (pinfunction "STAT_1") (pintype "unspecified"))
    )
    (net (code "53") (name "Net-(R6-Pad2)") (class "Default")
      (node (ref "R6") (pin "2") (pinfunction "2_2") (pintype "unspecified"))
      (node (ref "SW2") (pin "1") (pinfunction "1_1") (pintype "unspecified"))
    )
    (net (code "54") (name "Net-(RF1-SIN)") (class "Default")
      (node (ref "RF1") (pin "2") (pinfunction "SIN_2") (pintype "unspecified"))
      (node (ref "U2") (pin "9") (pinfunction "RF_9") (pintype "unspecified"))
    )
    (net (code "55") (name "Net-(U6-L1)") (class "Default")
      (node (ref "L2") (pin "1") (pinfunction "1_1") (pintype "unspecified"))
      (node (ref "U6") (pin "4") (pinfunction "L1_4") (pintype "unspecified"))
    )
    (net (code "56") (name "Net-(U6-L2)") (class "Default")
      (node (ref "L2") (pin "2") (pinfunction "2_2") (pintype "unspecified"))
      (node (ref "U6") (pin "2") (pinfunction "L2_2") (pintype "unspecified"))
    )
    (net (code "57") (name "Net-(U14-USB_DM)") (class "Default")
      (node (ref "R4") (pin "2") (pinfunction "2_2") (pintype "unspecified"))
      (node (ref "U14") (pin "46") (pinfunction "USB_DM_46") (pintype "bidirectional"))
    )
    (net (code "58") (name "Net-(U14-USB_DP)") (class "Default")
      (node (ref "R5") (pin "2") (pinfunction "2_2") (pintype "unspecified"))
      (node (ref "U14") (pin "47") (pinfunction "USB_DP_47") (pintype "bidirectional"))
    )
    (net (code "59") (name "Net-(U15-PROG)") (class "Default")
      (node (ref "R8") (pin "2") (pinfunction "2_2") (pintype "unspecified"))
      (node (ref "U15") (pin "5") (pinfunction "PROG_5") (pintype "unspecified"))
    )
    (net (code "60") (name "Net-(U18-OA)") (class "Default")
      (node (ref "K2") (pin "10") (pinfunction "10_10") (pintype "unspecified"))
      (node (ref "U18") (pin "1") (pinfunction "OA_1") (pintype "unspecified"))
    )
    (net (code "61") (name "Net-(U18-OB)") (class "Default")
      (node (ref "K2") (pin "1") (pinfunction "1_1") (pintype "unspecified"))
      (node (ref "U18") (pin "4") (pinfunction "OB_4") (pintype "unspecified"))
    )
    (net (code "62") (name "QSPI_SCLK") (class "Default")
      (node (ref "U14") (pin "52") (pinfunction "QSPI_SCLK_52") (pintype "output"))
      (node (ref "U9") (pin "6") (pinfunction "CLK_6") (pintype "unspecified"))
    )
    (net (code "63") (name "QSPI_SD0") (class "Default")
      (node (ref "U14") (pin "53") (pinfunction "QSPI_SD0_53") (pintype "bidirectional"))
      (node (ref "U9") (pin "5") (pinfunction "DI(IO0)_5") (pintype "unspecified"))
    )
    (net (code "64") (name "QSPI_SD1") (class "Default")
      (node (ref "U14") (pin "55") (pinfunction "QSPI_SD1_55") (pintype "bidirectional"))
      (node (ref "U9") (pin "2") (pinfunction "DO(IO1)_2") (pintype "unspecified"))
    )
    (net (code "65") (name "QSPI_SD2") (class "Default")
      (node (ref "U14") (pin "54") (pinfunction "QSPI_SD2_54") (pintype "bidirectional"))
      (node (ref "U9") (pin "3") (pinfunction "WP#(IO2)_3") (pintype "unspecified"))
    )
    (net (code "66") (name "QSPI_SD3") (class "Default")
      (node (ref "U14") (pin "51") (pinfunction "QSPI_SD3_51") (pintype "bidirectional"))
      (node (ref "U9") (pin "7") (pinfunction "HOLD#orRESET#(IO3)_7") (pintype "unspecified"))
    )
    (net (code "67") (name "QSPI_SS") (class "Default")
      (node (ref "R11") (pin "1") (pinfunction "1_1") (pintype "unspecified"))
      (node (ref "R6") (pin "1") (pinfunction "1_1") (pintype "unspecified"))
      (node (ref "U14") (pin "56") (pinfunction "QSPI_SS_56") (pintype "bidirectional"))
      (node (ref "U9") (pin "1") (pinfunction "CS#_1") (pintype "unspecified"))
    )
    (net (code "68") (name "RUN") (class "Default")
      (node (ref "SW1") (pin "4") (pinfunction "4_4") (pintype "unspecified"))
      (node (ref "U14") (pin "26") (pinfunction "RUN_26") (pintype "input"))
    )
    (net (code "69") (name "SWCLK") (class "Default")
      (node (ref "H1") (pin "1") (pinfunction "1_1") (pintype "unspecified"))
      (node (ref "U14") (pin "24") (pinfunction "SWCLK_24") (pintype "output"))
    )
    (net (code "70") (name "SWD") (class "Default")
      (node (ref "H1") (pin "3") (pinfunction "3_3") (pintype "unspecified"))
      (node (ref "U14") (pin "25") (pinfunction "SWD_25") (pintype "bidirectional"))
    )
    (net (code "71") (name "USB_D+") (class "Default")
      (node (ref "R5") (pin "1") (pinfunction "1_1") (pintype "unspecified"))
      (node (ref "USB2") (pin "3") (pinfunction "Data+_3") (pintype "unspecified"))
    )
    (net (code "72") (name "USB_D-") (class "Default")
      (node (ref "R4") (pin "1") (pinfunction "1_1") (pintype "unspecified"))
      (node (ref "USB2") (pin "2") (pinfunction "Data-_2") (pintype "unspecified"))
    )
    (net (code "73") (name "VBUS") (class "Default")
      (node (ref "D1") (pin "2") (pinfunction "A_2") (pintype "unspecified"))
      (node (ref "D2") (pin "1") (pinfunction "K_1") (pintype "unspecified"))
      (node (ref "P3") (pin "2") (pinfunction "2_2") (pintype "input"))
      (node (ref "USB2") (pin "1") (pinfunction "VBUS_1") (pintype "unspecified"))
    )
    (net (code "74") (name "VSYS") (class "Default")
      (node (ref "C21") (pin "2") (pinfunction "2_2") (pintype "unspecified"))
      (node (ref "C3") (pin "2") (pinfunction "2_2") (pintype "unspecified"))
      (node (ref "D3") (pin "1") (pinfunction "K_1") (pintype "unspecified"))
      (node (ref "P3") (pin "4") (pinfunction "4_4") (pintype "input"))
      (node (ref "Q1") (pin "2") (pinfunction "S_2") (pintype "unspecified"))
      (node (ref "U6") (pin "5") (pinfunction "VIN_5") (pintype "unspecified"))
      (node (ref "U6") (pin "6") (pinfunction "EN_6") (pintype "unspecified"))
      (node (ref "U6") (pin "7") (pinfunction "PS/SYNC_7") (pintype "unspecified"))
      (node (ref "U6") (pin "8") (pinfunction "VINA_8") (pintype "unspecified"))
    )
    (net (code "75") (name "XIN") (class "Default")
      (node (ref "C17") (pin "2") (pinfunction "2_2") (pintype "unspecified"))
      (node (ref "U14") (pin "20") (pinfunction "XIN_20") (pintype "input"))
      (node (ref "U4") (pin "1") (pinfunction "1_1") (pintype "input"))
    )
    (net (code "76") (name "XOUT") (class "Default")
      (node (ref "R10") (pin "2") (pinfunction "2_2") (pintype "unspecified"))
      (node (ref "U14") (pin "21") (pinfunction "XOUT_21") (pintype "unspecified"))
    )
    (net (code "77") (name "unconnected-(K2-Pad5)") (class "Default")
      (node (ref "K2") (pin "5") (pinfunction "5_5") (pintype "unspecified+no_connect"))
    )
    (net (code "78") (name "unconnected-(K2-Pad6)") (class "Default")
      (node (ref "K2") (pin "6") (pinfunction "6_6") (pintype "unspecified+no_connect"))
    )
    (net (code "79") (name "unconnected-(SW1-Pad2)") (class "Default")
      (node (ref "SW1") (pin "2") (pinfunction "2_2") (pintype "unspecified+no_connect"))
    )
    (net (code "80") (name "unconnected-(SW1-Pad3)") (class "Default")
      (node (ref "SW1") (pin "3") (pinfunction "3_3") (pintype "unspecified+no_connect"))
    )
    (net (code "81") (name "unconnected-(SW2-Pad2)") (class "Default")
      (node (ref "SW2") (pin "2") (pinfunction "2_2") (pintype "unspecified+no_connect"))
    )
    (net (code "82") (name "unconnected-(SW2-Pad3)") (class "Default")
      (node (ref "SW2") (pin "3") (pinfunction "3_3") (pintype "unspecified+no_connect"))
    )
    (net (code "83") (name "unconnected-(U6-EP-Pad11)") (class "Default")
      (node (ref "U6") (pin "11") (pinfunction "EP_11") (pintype "unspecified+no_connect"))
    )
    (net (code "84") (name "unconnected-(U7-NC-Pad3)") (class "Default")
      (node (ref "U7") (pin "3") (pinfunction "NC_3") (pintype "unspecified+no_connect"))
    )
    (net (code "85") (name "unconnected-(U9-EP-Pad9)") (class "Default")
      (node (ref "U9") (pin "9") (pinfunction "EP_9") (pintype "unspecified+no_connect"))
    )
    (net (code "86") (name "unconnected-(USB2-ID-Pad4)") (class "Default")
      (node (ref "USB2") (pin "4") (pinfunction "ID_4") (pintype "unspecified+no_connect"))
    )
  )
)
